# TFCard.net
KiCad netlist of a schematic drawn in Altium Designer
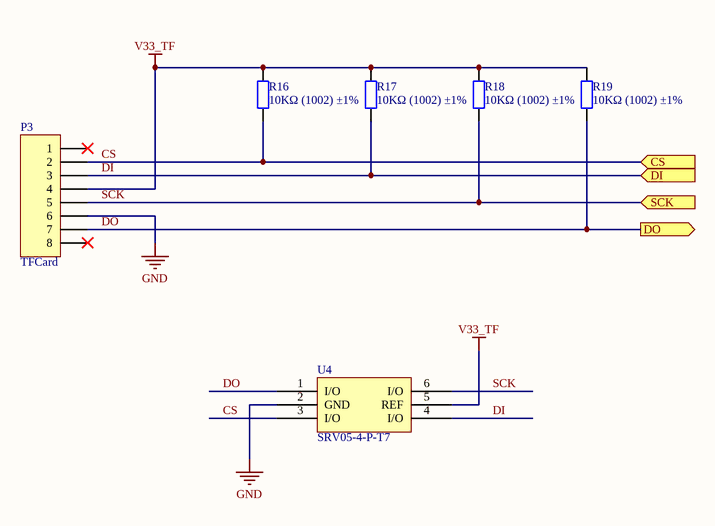
[diagram p0: TFCard.SchDoc]

(export (version "E")
  (design (tool "Eeschema 10.0.6"))
  (components
    (comp (ref "P3")
      (value "TFCard")
      (footprint "TF002")
      (description "Header, 8-Pin")
      (fields (field (name "PUBLISHER") "Altium Limited"))
      (libsource (lib "Miscellaneous Connectors") (part "Header 8"))
    )
    (comp (ref "R16")
      (value "10KΩ (1002) ±1%")
      (footprint "0402_R")
      (description "贴片电阻")
      (libsource (lib "Miscellaneous Devices LC") (part "0402 10KΩ (1002) 1%"))
    )
    (comp (ref "R17")
      (value "10KΩ (1002) ±1%")
      (footprint "0402_R")
      (description "贴片电阻")
      (libsource (lib "Miscellaneous Devices LC") (part "0402 10KΩ (1002) 1%"))
    )
    (comp (ref "R18")
      (value "10KΩ (1002) ±1%")
      (footprint "0402_R")
      (description "贴片电阻")
      (libsource (lib "Miscellaneous Devices LC") (part "0402 10KΩ (1002) 1%"))
    )
    (comp (ref "R19")
      (value "10KΩ (1002) ±1%")
      (footprint "0402_R")
      (description "贴片电阻")
      (libsource (lib "Miscellaneous Devices LC") (part "0402 10KΩ (1002) 1%"))
    )
    (comp (ref "U4")
      (value "SRV05-4-P-T7")
      (footprint "SOT-23-6")
      (description "TVS")
      (libsource (lib "Miscellaneous Devices LC") (part "SRV05-4-P-T7_[C85364]"))
    )
  )
  (nets
    (net (code "1") (name "/CS") (class "Default")
      (node (ref "P3") (pin "2") (pinfunction "2_2") (pintype "passive"))
      (node (ref "R16") (pin "1") (pinfunction "1_1") (pintype "passive"))
      (node (ref "U4") (pin "3") (pinfunction "I/O_3") (pintype "passive"))
    )
    (net (code "2") (name "/DI") (class "Default")
      (node (ref "P3") (pin "3") (pinfunction "3_3") (pintype "passive"))
      (node (ref "R17") (pin "1") (pinfunction "1_1") (pintype "passive"))
      (node (ref "U4") (pin "4") (pinfunction "I/O_4") (pintype "passive"))
    )
    (net (code "3") (name "/DO") (class "Default")
      (node (ref "P3") (pin "7") (pinfunction "7_7") (pintype "passive"))
      (node (ref "R19") (pin "1") (pinfunction "1_1") (pintype "passive"))
      (node (ref "U4") (pin "1") (pinfunction "I/O_1") (pintype "passive"))
    )
    (net (code "4") (name "/SCK") (class "Default")
      (node (ref "P3") (pin "5") (pinfunction "5_5") (pintype "passive"))
      (node (ref "R18") (pin "1") (pinfunction "1_1") (pintype "passive"))
      (node (ref "U4") (pin "6") (pinfunction "I/O_6") (pintype "passive"))
    )
    (net (code "5") (name "GND") (class "Default")
      (node (ref "P3") (pin "6") (pinfunction "6_6") (pintype "passive"))
      (node (ref "U4") (pin "2") (pinfunction "GND_2") (pintype "passive"))
    )
    (net (code "6") (name "V33_TF") (class "Default")
      (node (ref "P3") (pin "4") (pinfunction "4_4") (pintype "passive"))
      (node (ref "R16") (pin "2") (pinfunction "2_2") (pintype "passive"))
      (node (ref "R17") (pin "2") (pinfunction "2_2") (pintype "passive"))
      (node (ref "R18") (pin "2") (pinfunction "2_2") (pintype "passive"))
      (node (ref "R19") (pin "2") (pinfunction "2_2") (pintype "passive"))
      (node (ref "U4") (pin "5") (pinfunction "REF_5") (pintype "passive"))
    )
    (net (code "7") (name "unconnected-(P3-Pad1)") (class "Default")
      (node (ref "P3") (pin "1") (pinfunction "1_1") (pintype "passive+no_connect"))
    )
    (net (code "8") (name "unconnected-(P3-Pad8)") (class "Default")
      (node (ref "P3") (pin "8") (pinfunction "8_8") (pintype "passive+no_connect"))
    )
  )
)
